# WPD_PLL.net
KiCad netlist of a schematic drawn in Altium Designer
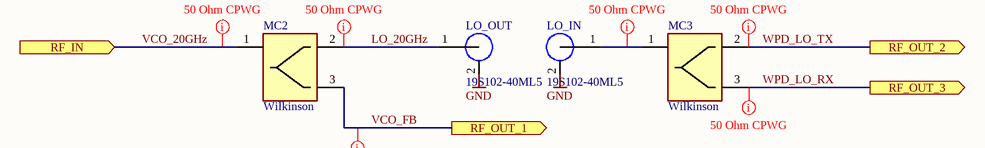
[diagram p0: WPD_PLL.SchDoc]

(export (version "E")
  (design (tool "Eeschema 10.0.6"))
  (components
    (comp (ref "LO_IN")
      (value "19S102-40ML5")
      (footprint "Rosenberger_19S102-40ML5")
      (fields (field (name "MANUFACTURER") "Rosenberger"))
      (libsource (lib "database_library") (part "Coaxial_Connector"))
    )
    (comp (ref "LO_OUT")
      (value "19S102-40ML5")
      (footprint "Rosenberger_19S102-40ML5")
      (fields (field (name "MANUFACTURER") "Rosenberger"))
      (libsource (lib "database_library") (part "Coaxial_Connector"))
    )
    (comp (ref "MC2")
      (value "Wilkinson")
      (footprint "Wilkinson_8GHz_RO4350B_254um")
      (libsource (lib "database_library") (part "Wilkinson"))
    )
    (comp (ref "MC3")
      (value "Wilkinson")
      (footprint "Wilkinson_8GHz_RO4350B_254um")
      (libsource (lib "database_library") (part "Wilkinson"))
    )
  )
  (nets
    (net (code "1") (name "/LO_20GHz") (class "Default")
      (node (ref "LO_OUT") (pin "1") (pintype "passive"))
      (node (ref "MC2") (pin "2") (pintype "passive"))
    )
    (net (code "2") (name "/VCO_20GHz") (class "Default") (node (ref "MC2") (pin "1") (pintype "passive")))
    (net (code "3") (name "/VCO_FB") (class "Default") (node (ref "MC2") (pin "3") (pintype "passive")))
    (net (code "4") (name "/WPD_LO_RX") (class "Default") (node (ref "MC3") (pin "3") (pintype "passive")))
    (net (code "5") (name "/WPD_LO_TX") (class "Default") (node (ref "MC3") (pin "2") (pintype "passive")))
    (net (code "6") (name "GND") (class "Default")
      (node (ref "LO_IN") (pin "2") (pintype "passive"))
      (node (ref "LO_OUT") (pin "2") (pintype "passive"))
    )
    (net (code "7") (name "Net-(LO_IN-Pad1)") (class "Default")
      (node (ref "LO_IN") (pin "1") (pintype "passive"))
      (node (ref "MC3") (pin "1") (pintype "passive"))
    )
  )
)
